# FRAM_memory.net
KiCad netlist of a schematic drawn in Altium Designer
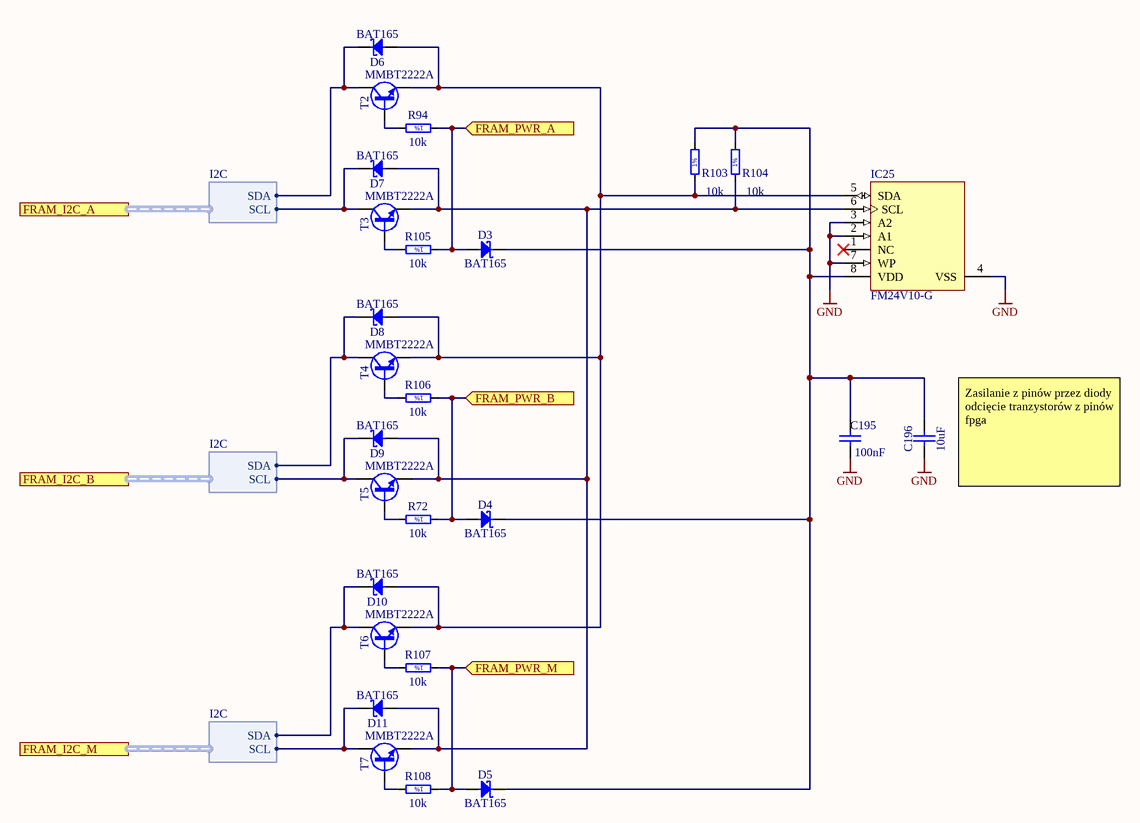
[diagram p0: FRAM_memory.SchDoc]

(export (version "E")
  (design (tool "Eeschema 10.0.6"))
  (components
    (comp (ref "C195")
      (value "100nF")
      (footprint "CAPC1608X87N")
      (description "Non-polarised capacitor")
      (fields
        (field (name "PART NUMBER") "CC0603_100NF_50V_10%_X7R")
        (field (name "VOLTAGE") "50V")
        (field (name "AUTHOR") "CERN DEM JLC")
      )
      (libsource (lib "Capacitors") (part "Capacitor - non polarized"))
    )
    (comp (ref "C196")
      (value "10uF")
      (footprint "CAPC1608X80N")
      (description "Non-polarised capacitor")
      (fields
        (field (name "PART NUMBER") "CC0603_10UF_16V_20%_X5R")
        (field (name "VOLTAGE") "16V")
        (field (name "AUTHOR") "CERN DEM MR")
      )
      (libsource (lib "Capacitors") (part "Capacitor - non polarized"))
    )
    (comp (ref "D3")
      (value "BAT165")
      (footprint "SOD2512X110N")
      (description "Schottky Diode")
      (fields
        (field (name "VOLTAGE") "40V")
        (field (name "POWER") "750mA")
        (field (name "AUTHOR") "CERN DEM JLC")
      )
      (libsource (lib "ICs And Semiconductors") (part "Diode Schottky"))
    )
    (comp (ref "D4")
      (value "BAT165")
      (footprint "SOD2512X110N")
      (description "Schottky Diode")
      (fields
        (field (name "VOLTAGE") "40V")
        (field (name "POWER") "750mA")
        (field (name "AUTHOR") "CERN DEM JLC")
      )
      (libsource (lib "ICs And Semiconductors") (part "Diode Schottky"))
    )
    (comp (ref "D5")
      (value "BAT165")
      (footprint "SOD2512X110N")
      (description "Schottky Diode")
      (fields
        (field (name "VOLTAGE") "40V")
        (field (name "POWER") "750mA")
        (field (name "AUTHOR") "CERN DEM JLC")
      )
      (libsource (lib "ICs And Semiconductors") (part "Diode Schottky"))
    )
    (comp (ref "D6")
      (value "BAT165")
      (footprint "SOD2512X110N")
      (description "Schottky Diode")
      (fields
        (field (name "VOLTAGE") "40V")
        (field (name "POWER") "750mA")
        (field (name "AUTHOR") "CERN DEM JLC")
      )
      (libsource (lib "ICs And Semiconductors") (part "Diode Schottky"))
    )
    (comp (ref "D7")
      (value "BAT165")
      (footprint "SOD2512X110N")
      (description "Schottky Diode")
      (fields
        (field (name "VOLTAGE") "40V")
        (field (name "POWER") "750mA")
        (field (name "AUTHOR") "CERN DEM JLC")
      )
      (libsource (lib "ICs And Semiconductors") (part "Diode Schottky"))
    )
    (comp (ref "D8")
      (value "BAT165")
      (footprint "SOD2512X110N")
      (description "Schottky Diode")
      (fields
        (field (name "VOLTAGE") "40V")
        (field (name "POWER") "750mA")
        (field (name "AUTHOR") "CERN DEM JLC")
      )
      (libsource (lib "ICs And Semiconductors") (part "Diode Schottky"))
    )
    (comp (ref "D9")
      (value "BAT165")
      (footprint "SOD2512X110N")
      (description "Schottky Diode")
      (fields
        (field (name "VOLTAGE") "40V")
        (field (name "POWER") "750mA")
        (field (name "AUTHOR") "CERN DEM JLC")
      )
      (libsource (lib "ICs And Semiconductors") (part "Diode Schottky"))
    )
    (comp (ref "D10")
      (value "BAT165")
      (footprint "SOD2512X110N")
      (description "Schottky Diode")
      (fields
        (field (name "VOLTAGE") "40V")
        (field (name "POWER") "750mA")
        (field (name "AUTHOR") "CERN DEM JLC")
      )
      (libsource (lib "ICs And Semiconductors") (part "Diode Schottky"))
    )
    (comp (ref "D11")
      (value "BAT165")
      (footprint "SOD2512X110N")
      (description "Schottky Diode")
      (fields
        (field (name "VOLTAGE") "40V")
        (field (name "POWER") "750mA")
        (field (name "AUTHOR") "CERN DEM JLC")
      )
      (libsource (lib "ICs And Semiconductors") (part "Diode Schottky"))
    )
    (comp (ref "IC25")
      (value "FM24V10-G")
      (footprint "SOIC127P600X175-8N")
      (fields (field (name "MANUFACTURER") "Cypress"))
      (libsource (lib "LIBRARY_SCH") (part "MEM_FM24V10-G"))
    )
    (comp (ref "R72")
      (value "10k")
      (footprint "RESC1608X55N")
      (description "Resistor - 1%")
      (fields
        (field (name "PART NUMBER") "R0603_10K_1%_0.1W_100PPM")
        (field (name "POWER") "0.1W")
        (field (name "AUTHOR") "CERN DEM JLC")
      )
      (libsource (lib "Resistors") (part "Resistor - 1%"))
    )
    (comp (ref "R94")
      (value "10k")
      (footprint "RESC1608X55N")
      (description "Resistor - 1%")
      (fields
        (field (name "PART NUMBER") "R0603_10K_1%_0.1W_100PPM")
        (field (name "POWER") "0.1W")
        (field (name "AUTHOR") "CERN DEM JLC")
      )
      (libsource (lib "Resistors") (part "Resistor - 1%"))
    )
    (comp (ref "R103")
      (value "10k")
      (footprint "RESC1608X55N")
      (description "Resistor - 1%")
      (fields
        (field (name "PART NUMBER") "R0603_10K_1%_0.1W_100PPM")
        (field (name "POWER") "0.1W")
        (field (name "AUTHOR") "CERN DEM JLC")
      )
      (libsource (lib "Resistors") (part "Resistor - 1%"))
    )
    (comp (ref "R104")
      (value "10k")
      (footprint "RESC1608X55N")
      (description "Resistor - 1%")
      (fields
        (field (name "PART NUMBER") "R0603_10K_1%_0.1W_100PPM")
        (field (name "POWER") "0.1W")
        (field (name "AUTHOR") "CERN DEM JLC")
      )
      (libsource (lib "Resistors") (part "Resistor - 1%"))
    )
    (comp (ref "R105")
      (value "10k")
      (footprint "RESC1608X55N")
      (description "Resistor - 1%")
      (fields
        (field (name "PART NUMBER") "R0603_10K_1%_0.1W_100PPM")
        (field (name "POWER") "0.1W")
        (field (name "AUTHOR") "CERN DEM JLC")
      )
      (libsource (lib "Resistors") (part "Resistor - 1%"))
    )
    (comp (ref "R106")
      (value "10k")
      (footprint "RESC1608X55N")
      (description "Resistor - 1%")
      (fields
        (field (name "PART NUMBER") "R0603_10K_1%_0.1W_100PPM")
        (field (name "POWER") "0.1W")
        (field (name "AUTHOR") "CERN DEM JLC")
      )
      (libsource (lib "Resistors") (part "Resistor - 1%"))
    )
    (comp (ref "R107")
      (value "10k")
      (footprint "RESC1608X55N")
      (description "Resistor - 1%")
      (fields
        (field (name "PART NUMBER") "R0603_10K_1%_0.1W_100PPM")
        (field (name "POWER") "0.1W")
        (field (name "AUTHOR") "CERN DEM JLC")
      )
      (libsource (lib "Resistors") (part "Resistor - 1%"))
    )
    (comp (ref "R108")
      (value "10k")
      (footprint "RESC1608X55N")
      (description "Resistor - 1%")
      (fields
        (field (name "PART NUMBER") "R0603_10K_1%_0.1W_100PPM")
        (field (name "POWER") "0.1W")
        (field (name "AUTHOR") "CERN DEM JLC")
      )
      (libsource (lib "Resistors") (part "Resistor - 1%"))
    )
    (comp (ref "T2")
      (value "MMBT2222A")
      (footprint "SOT95P240X130-3N")
      (description "NPN Transistor")
      (fields (field (name "MANUFACTURER") "FAIRCHILD SEMICONDUCTOR") (field (name "AUTHOR") "CERN DEM JLC"))
      (libsource (lib "ICs And Semiconductors") (part "NPN B1 E2 C3"))
    )
    (comp (ref "T3")
      (value "MMBT2222A")
      (footprint "SOT95P240X130-3N")
      (description "NPN Transistor")
      (fields (field (name "MANUFACTURER") "FAIRCHILD SEMICONDUCTOR") (field (name "AUTHOR") "CERN DEM JLC"))
      (libsource (lib "ICs And Semiconductors") (part "NPN B1 E2 C3"))
    )
    (comp (ref "T4")
      (value "MMBT2222A")
      (footprint "SOT95P240X130-3N")
      (description "NPN Transistor")
      (fields (field (name "MANUFACTURER") "FAIRCHILD SEMICONDUCTOR") (field (name "AUTHOR") "CERN DEM JLC"))
      (libsource (lib "ICs And Semiconductors") (part "NPN B1 E2 C3"))
    )
    (comp (ref "T5")
      (value "MMBT2222A")
      (footprint "SOT95P240X130-3N")
      (description "NPN Transistor")
      (fields (field (name "MANUFACTURER") "FAIRCHILD SEMICONDUCTOR") (field (name "AUTHOR") "CERN DEM JLC"))
      (libsource (lib "ICs And Semiconductors") (part "NPN B1 E2 C3"))
    )
    (comp (ref "T6")
      (value "MMBT2222A")
      (footprint "SOT95P240X130-3N")
      (description "NPN Transistor")
      (fields (field (name "MANUFACTURER") "FAIRCHILD SEMICONDUCTOR") (field (name "AUTHOR") "CERN DEM JLC"))
      (libsource (lib "ICs And Semiconductors") (part "NPN B1 E2 C3"))
    )
    (comp (ref "T7")
      (value "MMBT2222A")
      (footprint "SOT95P240X130-3N")
      (description "NPN Transistor")
      (fields (field (name "MANUFACTURER") "FAIRCHILD SEMICONDUCTOR") (field (name "AUTHOR") "CERN DEM JLC"))
      (libsource (lib "ICs And Semiconductors") (part "NPN B1 E2 C3"))
    )
  )
  (nets
    (net (code "2") (name "/FRAM_PWR_A") (class "Default")
      (node (ref "D3") (pin "2") (pinfunction "A_2") (pintype "passive"))
      (node (ref "R105") (pin "1") (pinfunction "1_1") (pintype "passive"))
      (node (ref "R94") (pin "1") (pinfunction "1_1") (pintype "passive"))
    )
    (net (code "3") (name "/FRAM_PWR_B") (class "Default")
      (node (ref "D4") (pin "2") (pinfunction "A_2") (pintype "passive"))
      (node (ref "R106") (pin "1") (pinfunction "1_1") (pintype "passive"))
      (node (ref "R72") (pin "1") (pinfunction "1_1") (pintype "passive"))
    )
    (net (code "4") (name "/FRAM_PWR_M") (class "Default")
      (node (ref "D5") (pin "2") (pinfunction "A_2") (pintype "passive"))
      (node (ref "R107") (pin "1") (pinfunction "1_1") (pintype "passive"))
      (node (ref "R108") (pin "1") (pinfunction "1_1") (pintype "passive"))
    )
    (net (code "6") (name "GND") (class "Default")
      (node (ref "C195") (pin "1") (pinfunction "1_1") (pintype "passive"))
      (node (ref "C196") (pin "1") (pinfunction "1_1") (pintype "passive"))
      (node (ref "IC25") (pin "2") (pinfunction "A1_2") (pintype "input"))
      (node (ref "IC25") (pin "3") (pinfunction "A2_3") (pintype "input"))
      (node (ref "IC25") (pin "4") (pinfunction "VSS_4") (pintype "power_in"))
      (node (ref "IC25") (pin "7") (pinfunction "WP_7") (pintype "input"))
    )
    (net (code "7") (name "Net-(D3-C)") (class "Default")
      (node (ref "C195") (pin "2") (pinfunction "2_2") (pintype "passive"))
      (node (ref "C196") (pin "2") (pinfunction "2_2") (pintype "passive"))
      (node (ref "D3") (pin "1") (pinfunction "C_1") (pintype "passive"))
      (node (ref "D4") (pin "1") (pinfunction "C_1") (pintype "passive"))
      (node (ref "D5") (pin "1") (pinfunction "C_1") (pintype "passive"))
      (node (ref "IC25") (pin "8") (pinfunction "VDD_8") (pintype "power_in"))
      (node (ref "R103") (pin "2") (pinfunction "2_2") (pintype "passive"))
      (node (ref "R104") (pin "2") (pinfunction "2_2") (pintype "passive"))
    )
    (net (code "8") (name "Net-(D6-C)") (class "Default")
      (node (ref "D6") (pin "1") (pinfunction "C_1") (pintype "passive"))
      (node (ref "T2") (pin "3") (pinfunction "C_3") (pintype "passive"))
    )
    (net (code "9") (name "Net-(D7-C)") (class "Default")
      (node (ref "D7") (pin "1") (pinfunction "C_1") (pintype "passive"))
      (node (ref "T3") (pin "3") (pinfunction "C_3") (pintype "passive"))
    )
    (net (code "10") (name "Net-(D8-C)") (class "Default")
      (node (ref "D8") (pin "1") (pinfunction "C_1") (pintype "passive"))
      (node (ref "T4") (pin "3") (pinfunction "C_3") (pintype "passive"))
    )
    (net (code "11") (name "Net-(D9-C)") (class "Default")
      (node (ref "D9") (pin "1") (pinfunction "C_1") (pintype "passive"))
      (node (ref "T5") (pin "3") (pinfunction "C_3") (pintype "passive"))
    )
    (net (code "12") (name "Net-(D10-A)") (class "Default")
      (node (ref "D10") (pin "2") (pinfunction "A_2") (pintype "passive"))
      (node (ref "D6") (pin "2") (pinfunction "A_2") (pintype "passive"))
      (node (ref "D8") (pin "2") (pinfunction "A_2") (pintype "passive"))
      (node (ref "IC25") (pin "5") (pinfunction "SDA_5") (pintype "bidirectional"))
      (node (ref "R103") (pin "1") (pinfunction "1_1") (pintype "passive"))
      (node (ref "T2") (pin "2") (pinfunction "E_2") (pintype "passive"))
      (node (ref "T4") (pin "2") (pinfunction "E_2") (pintype "passive"))
      (node (ref "T6") (pin "2") (pinfunction "E_2") (pintype "passive"))
    )
    (net (code "13") (name "Net-(D10-C)") (class "Default")
      (node (ref "D10") (pin "1") (pinfunction "C_1") (pintype "passive"))
      (node (ref "T6") (pin "3") (pinfunction "C_3") (pintype "passive"))
    )
    (net (code "14") (name "Net-(D11-A)") (class "Default")
      (node (ref "D11") (pin "2") (pinfunction "A_2") (pintype "passive"))
      (node (ref "D7") (pin "2") (pinfunction "A_2") (pintype "passive"))
      (node (ref "D9") (pin "2") (pinfunction "A_2") (pintype "passive"))
      (node (ref "IC25") (pin "6") (pinfunction "SCL_6") (pintype "input"))
      (node (ref "R104") (pin "1") (pinfunction "1_1") (pintype "passive"))
      (node (ref "T3") (pin "2") (pinfunction "E_2") (pintype "passive"))
      (node (ref "T5") (pin "2") (pinfunction "E_2") (pintype "passive"))
      (node (ref "T7") (pin "2") (pinfunction "E_2") (pintype "passive"))
    )
    (net (code "15") (name "Net-(D11-C)") (class "Default")
      (node (ref "D11") (pin "1") (pinfunction "C_1") (pintype "passive"))
      (node (ref "T7") (pin "3") (pinfunction "C_3") (pintype "passive"))
    )
    (net (code "16") (name "Net-(T2-B)") (class "Default")
      (node (ref "R94") (pin "2") (pinfunction "2_2") (pintype "passive"))
      (node (ref "T2") (pin "1") (pinfunction "B_1") (pintype "passive"))
    )
    (net (code "17") (name "Net-(T3-B)") (class "Default")
      (node (ref "R105") (pin "2") (pinfunction "2_2") (pintype "passive"))
      (node (ref "T3") (pin "1") (pinfunction "B_1") (pintype "passive"))
    )
    (net (code "18") (name "Net-(T4-B)") (class "Default")
      (node (ref "R106") (pin "2") (pinfunction "2_2") (pintype "passive"))
      (node (ref "T4") (pin "1") (pinfunction "B_1") (pintype "passive"))
    )
    (net (code "19") (name "Net-(T5-B)") (class "Default")
      (node (ref "R72") (pin "2") (pinfunction "2_2") (pintype "passive"))
      (node (ref "T5") (pin "1") (pinfunction "B_1") (pintype "passive"))
    )
    (net (code "20") (name "Net-(T6-B)") (class "Default")
      (node (ref "R107") (pin "2") (pinfunction "2_2") (pintype "passive"))
      (node (ref "T6") (pin "1") (pinfunction "B_1") (pintype "passive"))
    )
    (net (code "21") (name "Net-(T7-B)") (class "Default")
      (node (ref "R108") (pin "2") (pinfunction "2_2") (pintype "passive"))
      (node (ref "T7") (pin "1") (pinfunction "B_1") (pintype "passive"))
    )
    (net (code "22") (name "unconnected-(IC25-NC-Pad1)") (class "Default")
      (node (ref "IC25") (pin "1") (pinfunction "NC_1") (pintype "passive+no_connect"))
    )
  )
)
